# Sheet1.net
KiCad netlist of a schematic drawn in Altium Designer
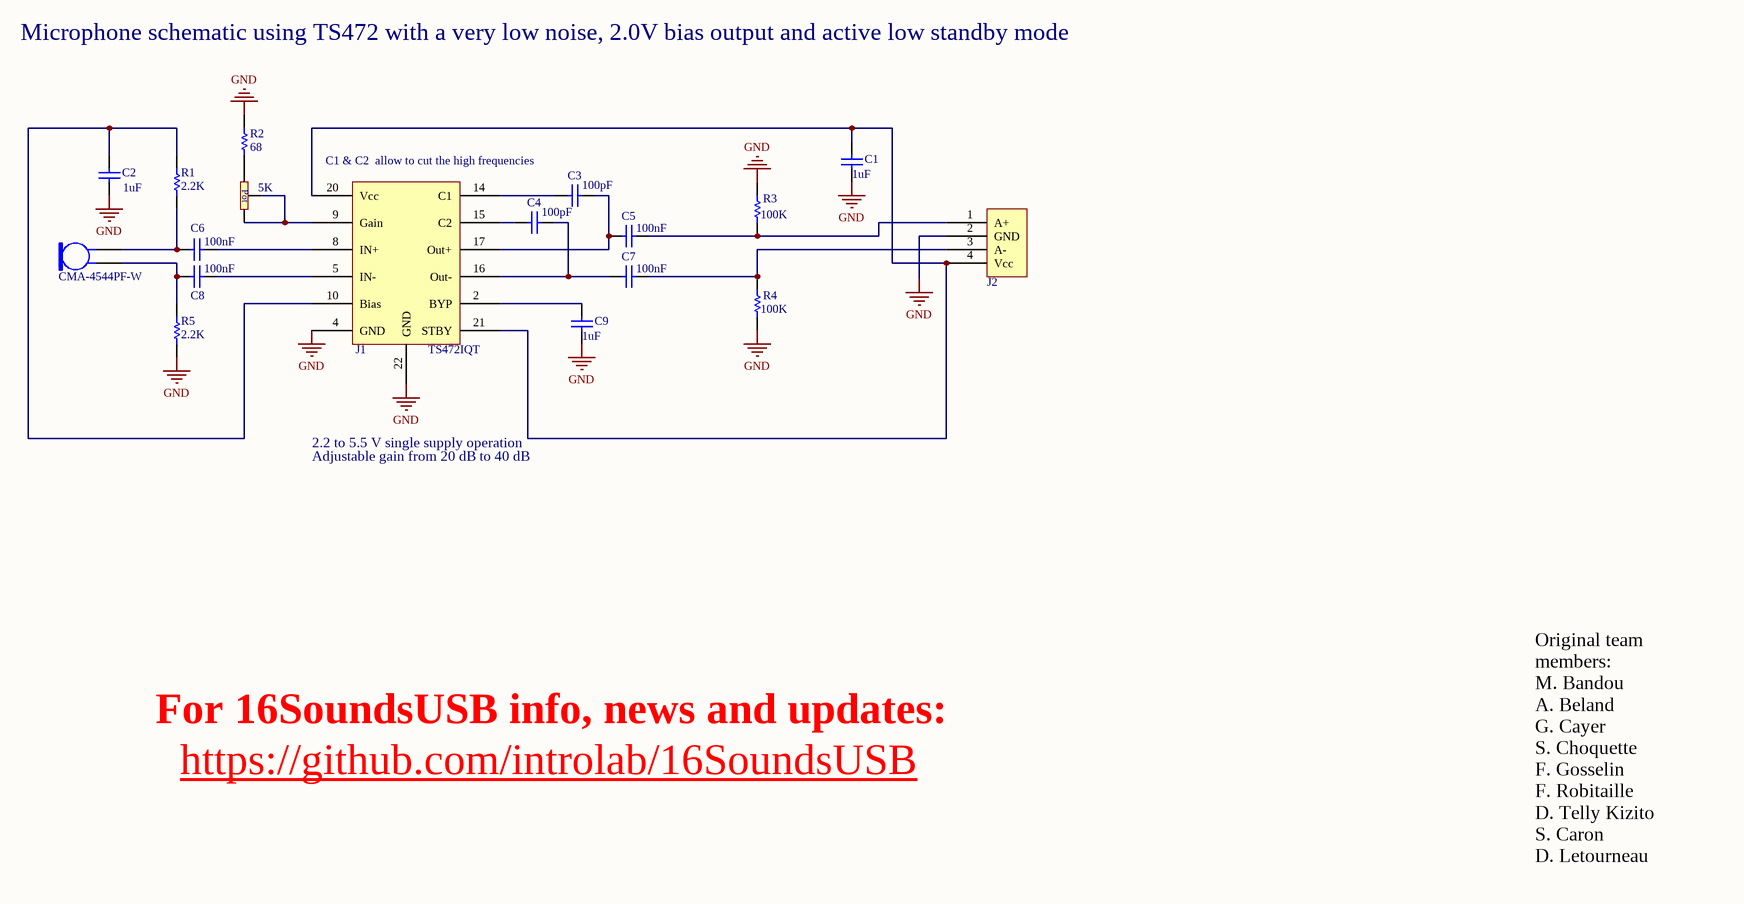
[diagram p0: Sheet1.SchDoc]

(export (version "E")
  (design (tool "Eeschema 10.0.6"))
  (components
    (comp (ref "C1")
      (value "1uF")
      (footprint "C0603")
      (description "Capacitor")
      (fields (field (name "MFG") "Murata Electronics North America"))
      (libsource (lib "Miscellaneous Devices") (part "Cap"))
    )
    (comp (ref "C2")
      (value "1uF")
      (footprint "C0603")
      (description "Capacitor")
      (fields (field (name "MFG") "Murata Electronics North America"))
      (libsource (lib "Miscellaneous Devices") (part "Cap"))
    )
    (comp (ref "C3")
      (value "100pF")
      (footprint "C0603")
      (description "Capacitor")
      (fields (field (name "MFG") "AVX Corporation"))
      (libsource (lib "Miscellaneous Devices") (part "Cap"))
    )
    (comp (ref "C4")
      (value "100pF")
      (footprint "C0603")
      (description "Capacitor")
      (fields (field (name "MFG") "AVX Corporation"))
      (libsource (lib "Miscellaneous Devices") (part "Cap"))
    )
    (comp (ref "C5")
      (value "100nF")
      (footprint "C0603")
      (description "Capacitor")
      (fields (field (name "MFG") "Kemet"))
      (libsource (lib "Miscellaneous Devices") (part "Cap"))
    )
    (comp (ref "C6")
      (value "100nF")
      (footprint "C0603")
      (description "Capacitor")
      (fields (field (name "MFG") "Kemet"))
      (libsource (lib "Miscellaneous Devices") (part "Cap"))
    )
    (comp (ref "C7")
      (value "100nF")
      (footprint "C0603")
      (description "Capacitor")
      (fields (field (name "MFG") "Kemet"))
      (libsource (lib "Miscellaneous Devices") (part "Cap"))
    )
    (comp (ref "C8")
      (value "100nF")
      (footprint "C0603")
      (description "Capacitor")
      (fields (field (name "MFG") "Kemet"))
      (libsource (lib "Miscellaneous Devices") (part "Cap"))
    )
    (comp (ref "C9")
      (value "1uF")
      (footprint "C0603")
      (description "Capacitor")
      (fields (field (name "MFG") "Murata Electronics North America"))
      (libsource (lib "Miscellaneous Devices") (part "Cap"))
    )
    (comp (ref "J1")
      (value "TS472IQT")
      (footprint "TS472")
      (description "IC Preamp Audio Mono AB 24QFN")
      (fields (field (name "MFG") "STMicroelectronics"))
      (libsource (lib "TS472") (part "TS472"))
    )
    (comp (ref "J2")
      (value "95503-6651")
      (footprint "RJ11 Micro")
      (description "Conn Jack 6P4C vert. unshielded")
      (fields (field (name "MFG") "Molex Connector Corporation"))
      (libsource (lib "RJ11-MIC") (part "RJ-11-MIC"))
    )
    (comp (ref "MK1")
      (value "CMA-4544PF-W")
      (footprint "Mic")
      (description "Microphone")
      (fields (field (name "MFG") "CUI Inc"))
      (libsource (lib "Miscellaneous Devices") (part "Mic2"))
    )
    (comp (ref "pot")
      (value "5K")
      (footprint "CT-94")
      (description "Trimmer Pot 5k Ohms 18 turns")
      (fields (field (name "MFG") "Copal Electronics Inc") (field (name "Comment") "CT94EW502"))
      (libsource (lib "CT-94") (part "CT-94"))
    )
    (comp (ref "R1")
      (value "2.2K")
      (footprint "R0603")
      (description "Resistor 1%")
      (fields (field (name "MFG") "Yageo") (field (name "Comment") "2.2k"))
      (libsource (lib "Miscellaneous Devices") (part "Res1"))
    )
    (comp (ref "R2")
      (value "68")
      (footprint "R0603")
      (description "Resistor 1%")
      (fields (field (name "MFG") "Yageo"))
      (libsource (lib "Miscellaneous Devices") (part "Res1"))
    )
    (comp (ref "R3")
      (value "100K")
      (footprint "R0603")
      (description "Resistor 1%")
      (fields (field (name "MFG") "Yageo"))
      (libsource (lib "Miscellaneous Devices") (part "Res1"))
    )
    (comp (ref "R4")
      (value "100K")
      (footprint "R0603")
      (description "Resistor 1%")
      (fields (field (name "MFG") "Yageo"))
      (libsource (lib "Miscellaneous Devices") (part "Res1"))
    )
    (comp (ref "R5")
      (value "2.2K")
      (footprint "R0603")
      (description "Resistor 1%")
      (fields (field (name "MFG") "Yageo"))
      (libsource (lib "Miscellaneous Devices") (part "Res1"))
    )
  )
  (nets
    (net (code "1") (name "GND") (class "Default")
      (node (ref "C1") (pin "2") (pinfunction "2_2") (pintype "passive"))
      (node (ref "C2") (pin "2") (pinfunction "2_2") (pintype "passive"))
      (node (ref "C9") (pin "2") (pinfunction "2_2") (pintype "passive"))
      (node (ref "J1") (pin "22") (pinfunction "GND_22") (pintype "passive"))
      (node (ref "J1") (pin "4") (pinfunction "GND_4") (pintype "passive"))
      (node (ref "J2") (pin "2") (pinfunction "GND_2") (pintype "passive"))
      (node (ref "R2") (pin "1") (pinfunction "1_1") (pintype "passive"))
      (node (ref "R3") (pin "2") (pinfunction "2_2") (pintype "passive"))
      (node (ref "R4") (pin "2") (pinfunction "2_2") (pintype "passive"))
      (node (ref "R5") (pin "2") (pinfunction "2_2") (pintype "passive"))
    )
    (net (code "2") (name "Net-(C6-Pad1)") (class "Default")
      (node (ref "C6") (pin "1") (pinfunction "1_1") (pintype "passive"))
      (node (ref "MK1") (pin "2") (pinfunction "2_2") (pintype "passive"))
      (node (ref "R1") (pin "2") (pinfunction "2_2") (pintype "passive"))
    )
    (net (code "3") (name "Net-(C8-Pad1)") (class "Default")
      (node (ref "C8") (pin "1") (pinfunction "1_1") (pintype "passive"))
      (node (ref "MK1") (pin "1") (pinfunction "1_1") (pintype "passive"))
      (node (ref "R5") (pin "1") (pinfunction "1_1") (pintype "passive"))
    )
    (net (code "4") (name "Net-(J1-BYP)") (class "Default")
      (node (ref "C9") (pin "1") (pinfunction "1_1") (pintype "passive"))
      (node (ref "J1") (pin "2") (pinfunction "BYP_2") (pintype "passive"))
    )
    (net (code "5") (name "Net-(J1-Bias)") (class "Default")
      (node (ref "C2") (pin "1") (pinfunction "1_1") (pintype "passive"))
      (node (ref "J1") (pin "10") (pinfunction "Bias_10") (pintype "passive"))
      (node (ref "R1") (pin "1") (pinfunction "1_1") (pintype "passive"))
    )
    (net (code "6") (name "Net-(J1-C1)") (class "Default")
      (node (ref "C3") (pin "1") (pinfunction "1_1") (pintype "passive"))
      (node (ref "J1") (pin "14") (pinfunction "C1_14") (pintype "passive"))
    )
    (net (code "7") (name "Net-(J1-C2)") (class "Default")
      (node (ref "C4") (pin "1") (pinfunction "1_1") (pintype "passive"))
      (node (ref "J1") (pin "15") (pinfunction "C2_15") (pintype "passive"))
    )
    (net (code "8") (name "Net-(J1-Gain)") (class "Default")
      (node (ref "J1") (pin "9") (pinfunction "Gain_9") (pintype "passive"))
      (node (ref "pot") (pin "2") (pinfunction "2_2") (pintype "passive"))
      (node (ref "pot") (pin "3") (pinfunction "3_3") (pintype "passive"))
    )
    (net (code "9") (name "Net-(J1-IN+)") (class "Default")
      (node (ref "C6") (pin "2") (pinfunction "2_2") (pintype "passive"))
      (node (ref "J1") (pin "8") (pinfunction "IN+_8") (pintype "passive"))
    )
    (net (code "10") (name "Net-(J1-IN-)") (class "Default")
      (node (ref "C8") (pin "2") (pinfunction "2_2") (pintype "passive"))
      (node (ref "J1") (pin "5") (pinfunction "IN-_5") (pintype "passive"))
    )
    (net (code "11") (name "Net-(J1-Out+)") (class "Default")
      (node (ref "C3") (pin "2") (pinfunction "2_2") (pintype "passive"))
      (node (ref "C5") (pin "1") (pinfunction "1_1") (pintype "passive"))
      (node (ref "J1") (pin "17") (pinfunction "Out+_17") (pintype "passive"))
    )
    (net (code "12") (name "Net-(J1-Out-)") (class "Default")
      (node (ref "C4") (pin "2") (pinfunction "2_2") (pintype "passive"))
      (node (ref "C7") (pin "1") (pinfunction "1_1") (pintype "passive"))
      (node (ref "J1") (pin "16") (pinfunction "Out-_16") (pintype "passive"))
    )
    (net (code "13") (name "Net-(J1-STBY)") (class "Default")
      (node (ref "C1") (pin "1") (pinfunction "1_1") (pintype "passive"))
      (node (ref "J1") (pin "20") (pinfunction "Vcc_20") (pintype "passive"))
      (node (ref "J1") (pin "21") (pinfunction "STBY_21") (pintype "passive"))
      (node (ref "J2") (pin "4") (pinfunction "Vcc_4") (pintype "passive"))
    )
    (net (code "14") (name "Net-(J2-A+)") (class "Default")
      (node (ref "C5") (pin "2") (pinfunction "2_2") (pintype "passive"))
      (node (ref "J2") (pin "1") (pinfunction "A+_1") (pintype "passive"))
      (node (ref "R3") (pin "1") (pinfunction "1_1") (pintype "passive"))
    )
    (net (code "15") (name "Net-(J2-A-)") (class "Default")
      (node (ref "C7") (pin "2") (pinfunction "2_2") (pintype "passive"))
      (node (ref "J2") (pin "3") (pinfunction "A-_3") (pintype "passive"))
      (node (ref "R4") (pin "1") (pinfunction "1_1") (pintype "passive"))
    )
    (net (code "16") (name "Net-(R2-Pad2)") (class "Default")
      (node (ref "R2") (pin "2") (pinfunction "2_2") (pintype "passive"))
      (node (ref "pot") (pin "1") (pinfunction "1_1") (pintype "passive"))
    )
  )
)
